# akabeacon_square_type1_da14580.net
KiCad netlist of a schematic drawn in EAGLE
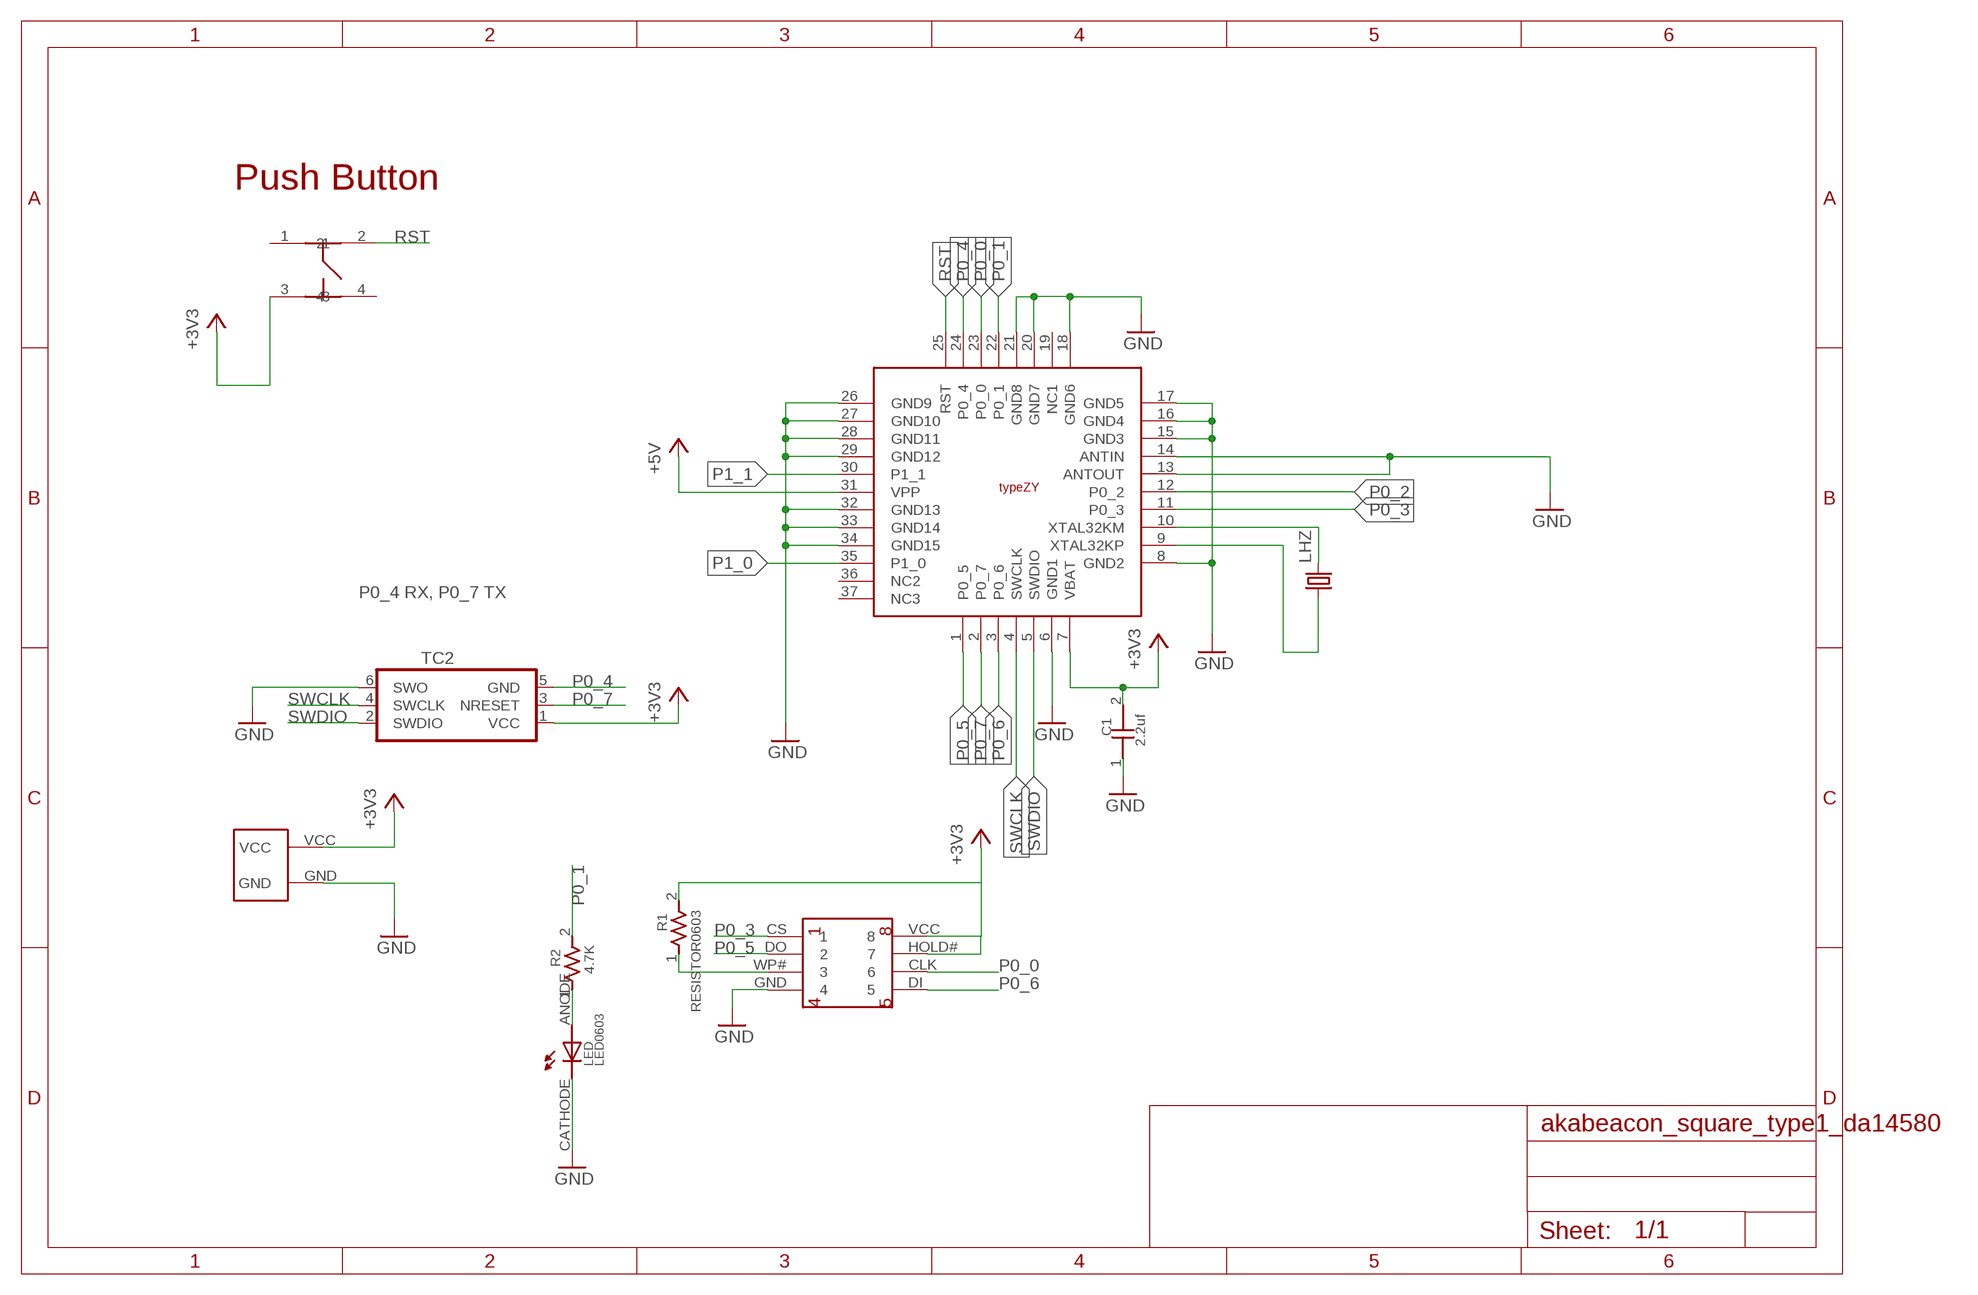
[diagram p0: schematic, sheet 1]

(export (version "E")
  (design (tool "Eeschema 10.0.6"))
  (components
    (comp (ref "C1")
      (value "2.2uf")
      (footprint "eagle-import:0603")
      (libsource (lib "eagle-import") (part "CAPACITOR0603"))
    )
    (comp (ref "LED")
      (value "LED0603")
      (footprint "eagle-import:0603")
      (libsource (lib "eagle-import") (part "LED0603"))
    )
    (comp (ref "LHZ")
      (value "FC-12M")
      (footprint "eagle-import:FC-12M")
      (libsource (lib "eagle-import") (part "FC-12M"))
    )
    (comp (ref "R1")
      (value "RESISTOR0603")
      (footprint "eagle-import:0603")
      (libsource (lib "eagle-import") (part "RESISTOR0603"))
    )
    (comp (ref "R2")
      (value "4.7K")
      (footprint "eagle-import:0603")
      (libsource (lib "eagle-import") (part "RESISTOR0603"))
    )
    (comp (ref "TC2")
      (value "TC2030-IDC-NL")
      (footprint "eagle-import:TC2030-IDC-NL")
      (libsource (lib "eagle-import") (part "TC2030-IDC-NL"))
    )
    (comp (ref "U$2")
      (value "SQUARE-TYPE1")
      (footprint "eagle-import:SQUARE-TYPE1-TC2030")
      (libsource (lib "eagle-import") (part "SQUARE-TYPE1"))
    )
    (comp (ref "U$3")
      (value "FLASH-MEMORY-2M(WINBOND)")
      (footprint "eagle-import:FLASH-MEMORY-2M(WINBOND)")
      (libsource (lib "eagle-import") (part "FLASH-MEMORY-2M(WINBOND)"))
    )
    (comp (ref "U$7")
      (value "SWICTH-4P(KMR2)")
      (footprint "eagle-import:SWITCH-4P(KMR2)")
      (libsource (lib "eagle-import") (part "SWICTH-4P(KMR2)"))
    )
    (comp (ref "U$9")
      (value "MURATA-TYPEZY")
      (footprint "eagle-import:MURATA_TYPEZY")
      (libsource (lib "eagle-import") (part "MURATA-TYPEZY"))
    )
  )
  (nets
    (net (code "1") (name "+3V3") (class "Default")
      (node (ref "C1") (pin "2") (pinfunction "2_2") (pintype "passive"))
      (node (ref "R1") (pin "2") (pinfunction "2_2") (pintype "passive"))
      (node (ref "TC2") (pin "1") (pinfunction "VCC_1") (pintype "passive"))
      (node (ref "U$2") (pin "VCC") (pinfunction "VCC_VCC") (pintype "bidirectional"))
      (node (ref "U$3") (pin "HOLD#") (pinfunction "7_HOLD#") (pintype "bidirectional"))
      (node (ref "U$3") (pin "VCC") (pinfunction "8_VCC") (pintype "bidirectional"))
      (node (ref "U$7") (pin "3") (pinfunction "3_3") (pintype "bidirectional"))
      (node (ref "U$9") (pin "7") (pinfunction "VBAT_7") (pintype "bidirectional"))
    )
    (net (code "2") (name "+5V") (class "Default")
      (node (ref "U$9") (pin "31") (pinfunction "VPP_31") (pintype "bidirectional"))
    )
    (net (code "3") (name "GND") (class "Default")
      (node (ref "C1") (pin "1") (pinfunction "1_1") (pintype "passive"))
      (node (ref "LED") (pin "CATHODE") (pinfunction "CATHODE_CATHODE") (pintype "passive"))
      (node (ref "TC2") (pin "6") (pinfunction "SWO_6") (pintype "passive"))
      (node (ref "U$2") (pin "GND") (pinfunction "GND_GND") (pintype "bidirectional"))
      (node (ref "U$3") (pin "GND") (pinfunction "4_GND") (pintype "bidirectional"))
      (node (ref "U$9") (pin "13") (pinfunction "ANTOUT_13") (pintype "bidirectional"))
      (node (ref "U$9") (pin "14") (pinfunction "ANTIN_14") (pintype "bidirectional"))
      (node (ref "U$9") (pin "15") (pinfunction "GND3_15") (pintype "bidirectional"))
      (node (ref "U$9") (pin "16") (pinfunction "GND4_16") (pintype "bidirectional"))
      (node (ref "U$9") (pin "17") (pinfunction "GND5_17") (pintype "bidirectional"))
      (node (ref "U$9") (pin "18") (pinfunction "GND6_18") (pintype "bidirectional"))
      (node (ref "U$9") (pin "20") (pinfunction "GND7_20") (pintype "bidirectional"))
      (node (ref "U$9") (pin "21") (pinfunction "GND8_21") (pintype "bidirectional"))
      (node (ref "U$9") (pin "26") (pinfunction "GND9_26") (pintype "bidirectional"))
      (node (ref "U$9") (pin "27") (pinfunction "GND10_27") (pintype "bidirectional"))
      (node (ref "U$9") (pin "28") (pinfunction "GND11_28") (pintype "bidirectional"))
      (node (ref "U$9") (pin "29") (pinfunction "GND12_29") (pintype "bidirectional"))
      (node (ref "U$9") (pin "32") (pinfunction "GND13_32") (pintype "bidirectional"))
      (node (ref "U$9") (pin "33") (pinfunction "GND14_33") (pintype "bidirectional"))
      (node (ref "U$9") (pin "34") (pinfunction "GND15_34") (pintype "bidirectional"))
      (node (ref "U$9") (pin "6") (pinfunction "GND1_6") (pintype "bidirectional"))
      (node (ref "U$9") (pin "8") (pinfunction "GND2_8") (pintype "bidirectional"))
    )
    (net (code "4") (name "Net-(LED-PadANODE)") (class "Default")
      (node (ref "LED") (pin "ANODE") (pinfunction "ANODE_ANODE") (pintype "passive"))
      (node (ref "R2") (pin "1") (pinfunction "1_1") (pintype "passive"))
    )
    (net (code "5") (name "Net-(U$3-3)") (class "Default")
      (node (ref "R1") (pin "1") (pinfunction "1_1") (pintype "passive"))
      (node (ref "U$3") (pin "WP#") (pinfunction "3_WP#") (pintype "bidirectional"))
    )
    (net (code "6") (name "Net-(U$9-XTAL32KM)") (class "Default")
      (node (ref "LHZ") (pin "2") (pinfunction "2_2") (pintype "passive"))
      (node (ref "U$9") (pin "10") (pinfunction "XTAL32KM_10") (pintype "bidirectional"))
    )
    (net (code "7") (name "Net-(U$9-XTAL32KP)") (class "Default")
      (node (ref "LHZ") (pin "1") (pinfunction "1_1") (pintype "passive"))
      (node (ref "U$9") (pin "9") (pinfunction "XTAL32KP_9") (pintype "bidirectional"))
    )
    (net (code "8") (name "P0_0") (class "Default")
      (node (ref "U$3") (pin "CLK") (pinfunction "6_CLK") (pintype "bidirectional"))
      (node (ref "U$9") (pin "23") (pinfunction "P0_0_23") (pintype "bidirectional"))
    )
    (net (code "9") (name "P0_1") (class "Default")
      (node (ref "R2") (pin "2") (pinfunction "2_2") (pintype "passive"))
      (node (ref "U$9") (pin "22") (pinfunction "P0_1_22") (pintype "bidirectional"))
    )
    (net (code "10") (name "P0_2") (class "Default")
      (node (ref "U$9") (pin "12") (pinfunction "P0_2_12") (pintype "bidirectional"))
    )
    (net (code "11") (name "P0_3") (class "Default")
      (node (ref "U$3") (pin "CS") (pinfunction "1_CS") (pintype "bidirectional"))
      (node (ref "U$9") (pin "11") (pinfunction "P0_3_11") (pintype "bidirectional"))
    )
    (net (code "12") (name "P0_4") (class "Default")
      (node (ref "TC2") (pin "5") (pinfunction "GND_5") (pintype "passive"))
      (node (ref "U$9") (pin "24") (pinfunction "P0_4_24") (pintype "bidirectional"))
    )
    (net (code "13") (name "P0_5") (class "Default")
      (node (ref "U$3") (pin "DO") (pinfunction "2_DO") (pintype "bidirectional"))
      (node (ref "U$9") (pin "1") (pinfunction "P0_5_1") (pintype "bidirectional"))
    )
    (net (code "14") (name "P0_6") (class "Default")
      (node (ref "U$3") (pin "DI") (pinfunction "5_DI") (pintype "bidirectional"))
      (node (ref "U$9") (pin "3") (pinfunction "P0_6_3") (pintype "bidirectional"))
    )
    (net (code "15") (name "P0_7") (class "Default")
      (node (ref "TC2") (pin "3") (pinfunction "NRESET_3") (pintype "passive"))
      (node (ref "U$9") (pin "2") (pinfunction "P0_7_2") (pintype "bidirectional"))
    )
    (net (code "16") (name "P1_0") (class "Default")
      (node (ref "U$9") (pin "35") (pinfunction "P1_0_35") (pintype "bidirectional"))
    )
    (net (code "17") (name "P1_1") (class "Default")
      (node (ref "U$9") (pin "30") (pinfunction "P1_1_30") (pintype "bidirectional"))
    )
    (net (code "18") (name "RST") (class "Default")
      (node (ref "U$7") (pin "2") (pinfunction "2_2") (pintype "bidirectional"))
      (node (ref "U$9") (pin "25") (pinfunction "RST_25") (pintype "bidirectional"))
    )
    (net (code "19") (name "SWCLK") (class "Default")
      (node (ref "TC2") (pin "4") (pinfunction "SWCLK_4") (pintype "passive"))
      (node (ref "U$9") (pin "4") (pinfunction "SWCLK_4") (pintype "bidirectional"))
    )
    (net (code "20") (name "SWDIO") (class "Default")
      (node (ref "TC2") (pin "2") (pinfunction "SWDIO_2") (pintype "passive"))
      (node (ref "U$9") (pin "5") (pinfunction "SWDIO_5") (pintype "bidirectional"))
    )
    (net (code "21") (name "unconnected-(U$7-Pad1)") (class "Default")
      (node (ref "U$7") (pin "1") (pinfunction "1_1") (pintype "bidirectional"))
    )
    (net (code "22") (name "unconnected-(U$7-Pad4)") (class "Default")
      (node (ref "U$7") (pin "4") (pinfunction "4_4") (pintype "bidirectional"))
    )
    (net (code "23") (name "unconnected-(U$9-NC1-Pad19)") (class "Default")
      (node (ref "U$9") (pin "19") (pinfunction "NC1_19") (pintype "bidirectional"))
    )
    (net (code "24") (name "unconnected-(U$9-NC2-Pad36)") (class "Default")
      (node (ref "U$9") (pin "36") (pinfunction "NC2_36") (pintype "bidirectional"))
    )
    (net (code "25") (name "unconnected-(U$9-NC3-Pad37)") (class "Default")
      (node (ref "U$9") (pin "37") (pinfunction "NC3_37") (pintype "bidirectional"))
    )
  )
)
